# ProPrj___2025-10-22.net
KiCad netlist of a schematic drawn in EasyEDA Pro
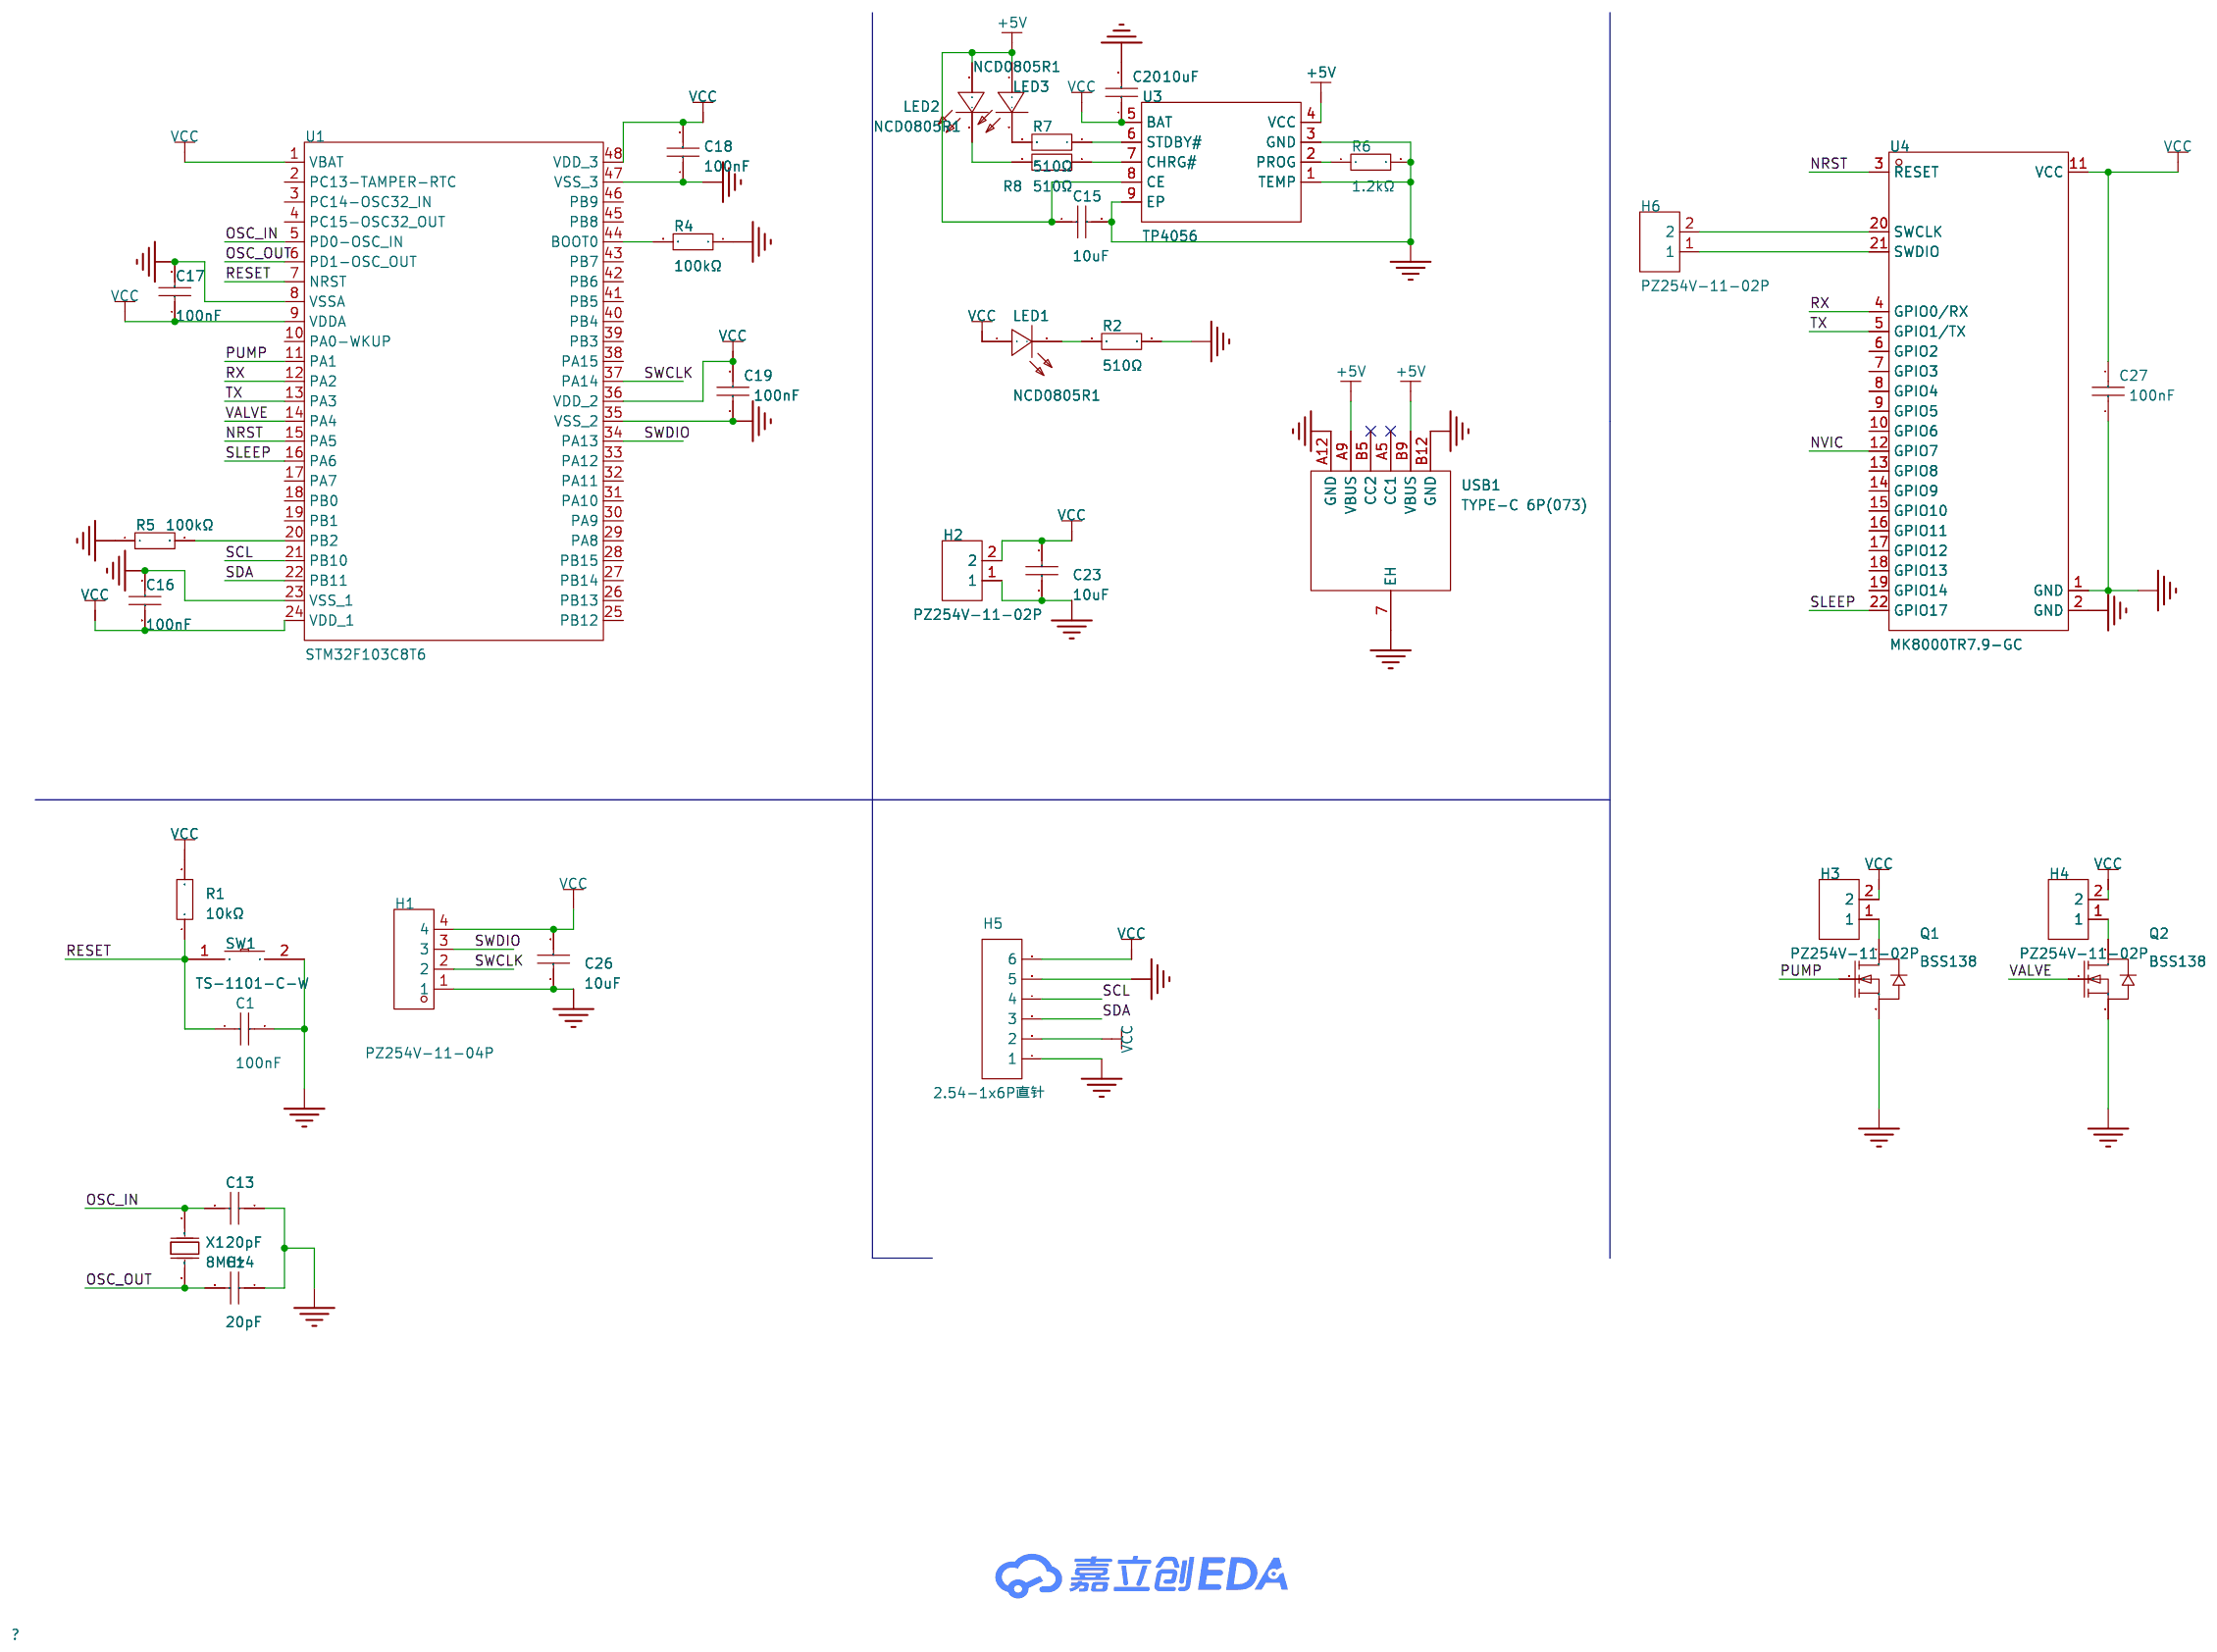
[diagram p0: schematic sheet]

(export (version "E")
  (design (tool "Eeschema 10.0.6"))
  (components
    (comp (ref "C1")
      (value "100nF")
      (footprint "easyedapro:C0805")
      (description "容值:100nF;精度:±10%;额定电压:50V;材质(温度系数):X7R;")
      (fields
        (field (name "Manufacturer Part") "CL21B104KBCNNNC")
        (field (name "Manufacturer") "SAMSUNG(三星)")
      )
      (libsource (lib "easyedapro") (part "CL21B104KBCNNNC"))
    )
    (comp (ref "C13")
      (value "20pF")
      (footprint "easyedapro:C0805")
      (description "容值:20pF;精度:±5%;额定电压:50V;材质(温度系数):C0G;")
      (fields
        (field (name "Manufacturer Part") "CL21C200JBANNNC")
        (field (name "Manufacturer") "SAMSUNG(三星)")
      )
      (libsource (lib "easyedapro") (part "CL21C200JBANNNC"))
    )
    (comp (ref "C14")
      (value "20pF")
      (footprint "easyedapro:C0805")
      (description "容值:20pF;精度:±5%;额定电压:50V;材质(温度系数):C0G;")
      (fields
        (field (name "Manufacturer Part") "CL21C200JBANNNC")
        (field (name "Manufacturer") "SAMSUNG(三星)")
      )
      (libsource (lib "easyedapro") (part "CL21C200JBANNNC"))
    )
    (comp (ref "C15")
      (value "10uF")
      (footprint "easyedapro:C0805")
      (description "容值:10uF;精度:±10%;额定电压:16V;温度系数:X5R;")
      (fields
        (field (name "Manufacturer Part") "CL21A106KOQNNNE")
        (field (name "Manufacturer") "SAMSUNG(三星)")
      )
      (libsource (lib "easyedapro") (part "CL21A106KOQNNNE"))
    )
    (comp (ref "C16")
      (value "100nF")
      (footprint "easyedapro:C0805")
      (description "容值:100nF;精度:±10%;额定电压:50V;材质(温度系数):X7R;")
      (fields
        (field (name "Manufacturer Part") "CL21B104KBCNNNC")
        (field (name "Manufacturer") "SAMSUNG(三星)")
      )
      (libsource (lib "easyedapro") (part "CL21B104KBCNNNC"))
    )
    (comp (ref "C17")
      (value "100nF")
      (footprint "easyedapro:C0805")
      (description "容值:100nF;精度:±10%;额定电压:50V;材质(温度系数):X7R;")
      (fields
        (field (name "Manufacturer Part") "CL21B104KBCNNNC")
        (field (name "Manufacturer") "SAMSUNG(三星)")
      )
      (libsource (lib "easyedapro") (part "CL21B104KBCNNNC"))
    )
    (comp (ref "C18")
      (value "100nF")
      (footprint "easyedapro:C0805")
      (description "容值:100nF;精度:±10%;额定电压:50V;材质(温度系数):X7R;")
      (fields
        (field (name "Manufacturer Part") "CL21B104KBCNNNC")
        (field (name "Manufacturer") "SAMSUNG(三星)")
      )
      (libsource (lib "easyedapro") (part "CL21B104KBCNNNC"))
    )
    (comp (ref "C19")
      (value "100nF")
      (footprint "easyedapro:C0805")
      (description "容值:100nF;精度:±10%;额定电压:50V;材质(温度系数):X7R;")
      (fields
        (field (name "Manufacturer Part") "CL21B104KBCNNNC")
        (field (name "Manufacturer") "SAMSUNG(三星)")
      )
      (libsource (lib "easyedapro") (part "CL21B104KBCNNNC"))
    )
    (comp (ref "C20")
      (value "10uF")
      (footprint "easyedapro:C0805")
      (description "容值:10uF;精度:±10%;额定电压:16V;温度系数:X5R;")
      (fields
        (field (name "Manufacturer Part") "CL21A106KOQNNNE")
        (field (name "Manufacturer") "SAMSUNG(三星)")
      )
      (libsource (lib "easyedapro") (part "CL21A106KOQNNNE"))
    )
    (comp (ref "C23")
      (value "10uF")
      (footprint "easyedapro:C0805")
      (description "容值:10uF;精度:±10%;额定电压:16V;温度系数:X5R;")
      (fields
        (field (name "Manufacturer Part") "CL21A106KOQNNNE")
        (field (name "Manufacturer") "SAMSUNG(三星)")
      )
      (libsource (lib "easyedapro") (part "CL21A106KOQNNNE"))
    )
    (comp (ref "C26")
      (value "10uF")
      (footprint "easyedapro:C0805")
      (description "容值:10uF;精度:±10%;额定电压:16V;温度系数:X5R;")
      (fields
        (field (name "Manufacturer Part") "CL21A106KOQNNNE")
        (field (name "Manufacturer") "SAMSUNG(三星)")
      )
      (libsource (lib "easyedapro") (part "CL21A106KOQNNNE"))
    )
    (comp (ref "C27")
      (value "100nF")
      (footprint "easyedapro:C0805")
      (description "容值:100nF;精度:±10%;额定电压:50V;材质(温度系数):X7R;")
      (fields
        (field (name "Manufacturer Part") "CL21B104KBCNNNC")
        (field (name "Manufacturer") "SAMSUNG(三星)")
      )
      (libsource (lib "easyedapro") (part "CL21B104KBCNNNC"))
    )
    (comp (ref "H1")
      (value "PZ254V-11-04P")
      (footprint "easyedapro:HDR-TH_4P-P2.54-V-M")
      (fields (field (name "Manufacturer") "XFCN(兴飞)"))
      (libsource (lib "easyedapro") (part "PZ254V-11-04P_C2691448"))
    )
    (comp (ref "H2")
      (value "PZ254V-11-02P")
      (footprint "easyedapro:HDR-TH_2P-P2.54-V-M")
      (fields (field (name "Manufacturer") "XFCN(兴飞)"))
      (libsource (lib "easyedapro") (part "PZ254V-11-02P"))
    )
    (comp (ref "H3")
      (value "PZ254V-11-02P")
      (footprint "easyedapro:HDR-TH_2P-P2.54-V-M")
      (fields (field (name "Manufacturer") "XFCN(兴飞)"))
      (libsource (lib "easyedapro") (part "PZ254V-11-02P"))
    )
    (comp (ref "H4")
      (value "PZ254V-11-02P")
      (footprint "easyedapro:HDR-TH_2P-P2.54-V-M")
      (fields (field (name "Manufacturer") "XFCN(兴飞)"))
      (libsource (lib "easyedapro") (part "PZ254V-11-02P"))
    )
    (comp (ref "H5")
      (value "2.54-1x6P直针")
      (footprint "easyedapro:HDR-TH_6P-P2.54-V-M-1")
      (fields (field (name "Manufacturer") "BOOMELE(博穆精密)"))
      (libsource (lib "easyedapro") (part "Header-Male-2.54_1x6"))
    )
    (comp (ref "H6")
      (value "PZ254V-11-02P")
      (footprint "easyedapro:HDR-TH_2P-P2.54-V-M")
      (fields (field (name "Manufacturer") "XFCN(兴飞)"))
      (libsource (lib "easyedapro") (part "PZ254V-11-02P"))
    )
    (comp (ref "LED1")
      (value "NCD0805R1")
      (footprint "easyedapro:LED0805-R-RD")
      (fields (field (name "Manufacturer") "国星光电"))
      (libsource (lib "easyedapro") (part "FC-2012HRK-620D"))
    )
    (comp (ref "LED2")
      (value "NCD0805R1")
      (footprint "easyedapro:LED0805-R-RD")
      (fields (field (name "Manufacturer") "国星光电"))
      (libsource (lib "easyedapro") (part "FC-2012HRK-620D"))
    )
    (comp (ref "LED3")
      (value "NCD0805R1")
      (footprint "easyedapro:LED0805-R-RD")
      (fields (field (name "Manufacturer") "国星光电"))
      (libsource (lib "easyedapro") (part "FC-2012HRK-620D"))
    )
    (comp (ref "Q1")
      (value "BSS138")
      (footprint "easyedapro:SOT-23-3_L2.9-W1.3-P1.90-LS2.4-BR")
      (fields (field (name "Manufacturer") "R+O(宏嘉诚)"))
      (libsource (lib "easyedapro") (part "BSS138_C7420339"))
    )
    (comp (ref "Q2")
      (value "BSS138")
      (footprint "easyedapro:SOT-23-3_L2.9-W1.3-P1.90-LS2.4-BR")
      (fields (field (name "Manufacturer") "R+O(宏嘉诚)"))
      (libsource (lib "easyedapro") (part "BSS138_C7420339"))
    )
    (comp (ref "R1")
      (value "10kΩ")
      (footprint "easyedapro:R0805")
      (description "电阻类型:厚膜电阻;阻值:10kΩ;精度:±1%;功率:125mW;工作电压:150V;温度系数:±100ppm/°C;")
      (fields
        (field (name "Manufacturer Part") "0805W8F1002T5E")
        (field (name "Manufacturer") "UNI-ROYAL(厚声)")
      )
      (libsource (lib "easyedapro") (part "0805W8F1002T5E"))
    )
    (comp (ref "R2")
      (value "510Ω")
      (footprint "easyedapro:R0805")
      (description "电阻类型:厚膜电阻;阻值:510Ω;精度:±1%;功率:125mW;最大工作电压:150V;温度系数:±100ppm/°C;")
      (fields
        (field (name "Manufacturer Part") "0805W8F5100T5E")
        (field (name "Manufacturer") "UNI-ROYAL(厚声)")
      )
      (libsource (lib "easyedapro") (part "0805W8F5100T5E"))
    )
    (comp (ref "R4")
      (value "100kΩ")
      (footprint "easyedapro:R0805")
      (description "电阻类型:厚膜电阻;阻值:100kΩ;精度:±1%;功率:125mW;工作电压:150V;温度系数:±100ppm/°C;")
      (fields
        (field (name "Manufacturer Part") "0805W8F1003T5E")
        (field (name "Manufacturer") "UNI-ROYAL(厚声)")
      )
      (libsource (lib "easyedapro") (part "0805W8F1003T5E_C149504"))
    )
    (comp (ref "R5")
      (value "100kΩ")
      (footprint "easyedapro:R0805")
      (description "电阻类型:厚膜电阻;阻值:100kΩ;精度:±1%;功率:125mW;工作电压:150V;温度系数:±100ppm/°C;")
      (fields
        (field (name "Manufacturer Part") "0805W8F1003T5E")
        (field (name "Manufacturer") "UNI-ROYAL(厚声)")
      )
      (libsource (lib "easyedapro") (part "0805W8F1003T5E_C149504"))
    )
    (comp (ref "R6")
      (value "1.2kΩ")
      (footprint "easyedapro:R0603")
      (description "电阻类型:厚膜电阻;阻值:1.2kΩ;精度:±1%;功率:100mW;工作电压:75V;温度系数:±100ppm/°C;")
      (fields
        (field (name "Manufacturer Part") "0603WAF1201T5E")
        (field (name "Manufacturer") "UNI-ROYAL(厚声)")
      )
      (libsource (lib "easyedapro") (part "0603WAF1201T5E"))
    )
    (comp (ref "R7")
      (value "510Ω")
      (footprint "easyedapro:R0805")
      (description "电阻类型:厚膜电阻;阻值:510Ω;精度:±1%;功率:125mW;最大工作电压:150V;温度系数:±100ppm/°C;")
      (fields
        (field (name "Manufacturer Part") "0805W8F5100T5E")
        (field (name "Manufacturer") "UNI-ROYAL(厚声)")
      )
      (libsource (lib "easyedapro") (part "0805W8F5100T5E"))
    )
    (comp (ref "R8")
      (value "510Ω")
      (footprint "easyedapro:R0805")
      (description "电阻类型:厚膜电阻;阻值:510Ω;精度:±1%;功率:125mW;最大工作电压:150V;温度系数:±100ppm/°C;")
      (fields
        (field (name "Manufacturer Part") "0805W8F5100T5E")
        (field (name "Manufacturer") "UNI-ROYAL(厚声)")
      )
      (libsource (lib "easyedapro") (part "0805W8F5100T5E"))
    )
    (comp (ref "SW1")
      (value "TS-1101-C-W")
      (footprint "easyedapro:SW-SMD_L6.0-W3.3-LS8.0")
      (fields (field (name "Manufacturer") "XKB Connectivity(中国星坤)"))
      (libsource (lib "easyedapro") (part "TS-1101-C-W"))
    )
    (comp (ref "U1")
      (value "STM32F103C8T6")
      (footprint "easyedapro:LQFP-48_L7.0-W7.0-P0.50-LS9.0-BL")
      (description "CPU内核:ARM-M3;CPU最大主频:72MHz;应用领域:-;")
      (fields (field (name "Manufacturer") "ST(意法半导体)"))
      (libsource (lib "easyedapro") (part "STM32F103C8T6"))
    )
    (comp (ref "U3")
      (value "TP4056")
      (footprint "easyedapro:ESOP-8_L4.9-W3.9-P1.27-LS6.0-BL-EP")
      (description "工作电压:3.7V~6.5V;最大充电电流:1A;电池类型:锂离子;电池节数:1;")
      (fields (field (name "Manufacturer") "UMW(友台半导体)"))
      (libsource (lib "easyedapro") (part "TP4056_C725790"))
    )
    (comp (ref "U4")
      (value "MK8000TR7.9-GC")
      (footprint "easyedapro:COMM-SMD_L26.3-W16.1_MK8000TR7.9-GC")
      (description "国产UWB测距模块电子围栏应用")
      (fields (field (name "Manufacturer") "Silicontra(硅传科技)"))
      (libsource (lib "easyedapro") (part "MK8000TR7.9-GC"))
    )
    (comp (ref "USB1")
      (value "TYPE-C 6P(073)")
      (footprint "easyedapro:TYPE-C-SMD_TYPE-C-6P-073")
      (description "连接器类型:Type-C;标准:USB 3.1;公母:母;安装方式:卧贴;触点数量:6P;端口数量:1;额定电流 - 电源:3A;工作温度范围:-25°C~+85°C;")
      (fields (field (name "Manufacturer") "SHOU HAN(首韩)"))
      (libsource (lib "easyedapro") (part "TYPE-C 6P(073)"))
    )
    (comp (ref "X1")
      (value "8MHz")
      (footprint "easyedapro:CRYSTAL-SMD_L11.5-W4.8-LS12.7")
      (description "晶振类型:贴片晶振;频率:8MHz;常温频差:±20ppm;负载电容:20pF;频率稳定度:±30ppm;")
      (fields (field (name "Manufacturer Part") "X49SM8MSD2SC") (field (name "Manufacturer") "YXC(扬兴晶振)"))
      (libsource (lib "easyedapro") (part "X49SM8MSD2SC"))
    )
  )
  (nets
    (net (code "1") (name "+5V") (class "Default")
      (node (ref "C15") (pin "1") (pinfunction "1_1") (pintype "input"))
      (node (ref "LED2") (pin "1") (pinfunction "+_1") (pintype "unspecified"))
      (node (ref "LED3") (pin "1") (pinfunction "+_1") (pintype "unspecified"))
      (node (ref "U3") (pin "4") (pinfunction "VCC_4") (pintype "unspecified"))
      (node (ref "U3") (pin "8") (pinfunction "CE_8") (pintype "unspecified"))
      (node (ref "USB1") (pin "A9") (pinfunction "VBUS_A9") (pintype "unspecified"))
      (node (ref "USB1") (pin "B9") (pinfunction "VBUS_B9") (pintype "unspecified"))
    )
    (net (code "2") (name "/NRST") (class "Default")
      (node (ref "U1") (pin "15") (pinfunction "PA5_15") (pintype "unspecified"))
      (node (ref "U4") (pin "3") (pinfunction "RESET_3") (pintype "unspecified"))
    )
    (net (code "3") (name "/NVIC") (class "Default")
      (node (ref "U4") (pin "12") (pinfunction "GPIO7_12") (pintype "unspecified"))
    )
    (net (code "4") (name "/OSC_IN") (class "Default")
      (node (ref "C13") (pin "2") (pinfunction "2_2") (pintype "input"))
      (node (ref "U1") (pin "5") (pinfunction "PD0-OSC_IN_5") (pintype "unspecified"))
      (node (ref "X1") (pin "1") (pinfunction "OSC1_1") (pintype "input"))
    )
    (net (code "5") (name "/OSC_OUT") (class "Default")
      (node (ref "C14") (pin "2") (pinfunction "2_2") (pintype "input"))
      (node (ref "U1") (pin "6") (pinfunction "PD1-OSC_OUT_6") (pintype "unspecified"))
      (node (ref "X1") (pin "2") (pinfunction "OSC2_2") (pintype "input"))
    )
    (net (code "6") (name "/PUMP") (class "Default")
      (node (ref "Q1") (pin "1") (pinfunction "G_1") (pintype "unspecified"))
      (node (ref "U1") (pin "11") (pinfunction "PA1_11") (pintype "unspecified"))
    )
    (net (code "7") (name "/RESET") (class "Default")
      (node (ref "C1") (pin "1") (pinfunction "1_1") (pintype "input"))
      (node (ref "R1") (pin "1") (pinfunction "1_1") (pintype "input"))
      (node (ref "SW1") (pin "1") (pinfunction "1_1") (pintype "unspecified"))
      (node (ref "U1") (pin "7") (pinfunction "NRST_7") (pintype "unspecified"))
    )
    (net (code "8") (name "/RX") (class "Default")
      (node (ref "U1") (pin "12") (pinfunction "PA2_12") (pintype "unspecified"))
      (node (ref "U4") (pin "4") (pinfunction "GPIO0/RX_4") (pintype "unspecified"))
    )
    (net (code "9") (name "/SCL") (class "Default")
      (node (ref "H5") (pin "4") (pinfunction "4_4") (pintype "input"))
      (node (ref "U1") (pin "21") (pinfunction "PB10_21") (pintype "unspecified"))
    )
    (net (code "10") (name "/SDA") (class "Default")
      (node (ref "H5") (pin "3") (pinfunction "3_3") (pintype "input"))
      (node (ref "U1") (pin "22") (pinfunction "PB11_22") (pintype "unspecified"))
    )
    (net (code "11") (name "/SLEEP") (class "Default")
      (node (ref "U1") (pin "16") (pinfunction "PA6_16") (pintype "unspecified"))
      (node (ref "U4") (pin "22") (pinfunction "GPIO17_22") (pintype "unspecified"))
    )
    (net (code "12") (name "/SWCLK") (class "Default")
      (node (ref "H1") (pin "2") (pinfunction "2_2") (pintype "unspecified"))
      (node (ref "U1") (pin "37") (pinfunction "PA14_37") (pintype "unspecified"))
    )
    (net (code "13") (name "/SWDIO") (class "Default")
      (node (ref "H1") (pin "3") (pinfunction "3_3") (pintype "unspecified"))
      (node (ref "U1") (pin "34") (pinfunction "PA13_34") (pintype "unspecified"))
    )
    (net (code "14") (name "/TX") (class "Default")
      (node (ref "U1") (pin "13") (pinfunction "PA3_13") (pintype "unspecified"))
      (node (ref "U4") (pin "5") (pinfunction "GPIO1/TX_5") (pintype "unspecified"))
    )
    (net (code "15") (name "/VALVE") (class "Default")
      (node (ref "Q2") (pin "1") (pinfunction "G_1") (pintype "unspecified"))
      (node (ref "U1") (pin "14") (pinfunction "PA4_14") (pintype "unspecified"))
    )
    (net (code "16") (name "GND") (class "Default")
      (node (ref "C1") (pin "2") (pinfunction "2_2") (pintype "input"))
      (node (ref "C13") (pin "1") (pinfunction "1_1") (pintype "input"))
      (node (ref "C14") (pin "1") (pinfunction "1_1") (pintype "input"))
      (node (ref "C15") (pin "2") (pinfunction "2_2") (pintype "input"))
      (node (ref "C16") (pin "1") (pinfunction "1_1") (pintype "input"))
      (node (ref "C17") (pin "2") (pinfunction "2_2") (pintype "input"))
      (node (ref "C18") (pin "1") (pinfunction "1_1") (pintype "input"))
      (node (ref "C19") (pin "1") (pinfunction "1_1") (pintype "input"))
      (node (ref "C20") (pin "2") (pinfunction "2_2") (pintype "input"))
      (node (ref "C23") (pin "1") (pinfunction "1_1") (pintype "input"))
      (node (ref "C26") (pin "1") (pinfunction "1_1") (pintype "input"))
      (node (ref "C27") (pin "1") (pinfunction "1_1") (pintype "input"))
      (node (ref "H1") (pin "1") (pinfunction "1_1") (pintype "unspecified"))
      (node (ref "H2") (pin "1") (pinfunction "1_1") (pintype "unspecified"))
      (node (ref "H5") (pin "1") (pinfunction "1_1") (pintype "input"))
      (node (ref "H5") (pin "5") (pinfunction "5_5") (pintype "input"))
      (node (ref "Q1") (pin "2") (pinfunction "S_2") (pintype "unspecified"))
      (node (ref "Q2") (pin "2") (pinfunction "S_2") (pintype "unspecified"))
      (node (ref "R2") (pin "2") (pinfunction "2_2") (pintype "input"))
      (node (ref "R4") (pin "1") (pinfunction "1_1") (pintype "unspecified"))
      (node (ref "R5") (pin "1") (pinfunction "1_1") (pintype "unspecified"))
      (node (ref "R6") (pin "2") (pinfunction "2_2") (pintype "input"))
      (node (ref "SW1") (pin "2") (pinfunction "2_2") (pintype "unspecified"))
      (node (ref "U1") (pin "23") (pinfunction "VSS_1_23") (pintype "unspecified"))
      (node (ref "U1") (pin "35") (pinfunction "VSS_2_35") (pintype "unspecified"))
      (node (ref "U1") (pin "47") (pinfunction "VSS_3_47") (pintype "unspecified"))
      (node (ref "U1") (pin "8") (pinfunction "VSSA_8") (pintype "unspecified"))
      (node (ref "U3") (pin "1") (pinfunction "TEMP_1") (pintype "unspecified"))
      (node (ref "U3") (pin "3") (pinfunction "GND_3") (pintype "unspecified"))
      (node (ref "U3") (pin "9") (pinfunction "EP_9") (pintype "unspecified"))
      (node (ref "U4") (pin "1") (pinfunction "GND_1") (pintype "unspecified"))
      (node (ref "U4") (pin "2") (pinfunction "GND_2") (pintype "unspecified"))
      (node (ref "USB1") (pin "7") (pinfunction "EH_7") (pintype "unspecified"))
      (node (ref "USB1") (pin "A12") (pinfunction "GND_A12") (pintype "unspecified"))
      (node (ref "USB1") (pin "B12") (pinfunction "GND_B12") (pintype "unspecified"))
    )
    (net (code "17") (name "Net-(LED1--)") (class "Default")
      (node (ref "LED1") (pin "2") (pinfunction "-_2") (pintype "unspecified"))
      (node (ref "R2") (pin "1") (pinfunction "1_1") (pintype "input"))
    )
    (net (code "18") (name "Net-(LED2--)") (class "Default")
      (node (ref "LED2") (pin "2") (pinfunction "-_2") (pintype "unspecified"))
      (node (ref "R8") (pin "2") (pinfunction "2_2") (pintype "input"))
    )
    (net (code "19") (name "Net-(LED3--)") (class "Default")
      (node (ref "LED3") (pin "2") (pinfunction "-_2") (pintype "unspecified"))
      (node (ref "R7") (pin "2") (pinfunction "2_2") (pintype "input"))
    )
    (net (code "20") (name "Net-(Q1-D)") (class "Default")
      (node (ref "H3") (pin "1") (pinfunction "1_1") (pintype "unspecified"))
      (node (ref "Q1") (pin "3") (pinfunction "D_3") (pintype "unspecified"))
    )
    (net (code "21") (name "Net-(Q2-D)") (class "Default")
      (node (ref "H4") (pin "1") (pinfunction "1_1") (pintype "unspecified"))
      (node (ref "Q2") (pin "3") (pinfunction "D_3") (pintype "unspecified"))
    )
    (net (code "22") (name "Net-(U1-BOOT0)") (class "Default")
      (node (ref "R4") (pin "2") (pinfunction "2_2") (pintype "unspecified"))
      (node (ref "U1") (pin "44") (pinfunction "BOOT0_44") (pintype "unspecified"))
    )
    (net (code "23") (name "Net-(U1-PB2)") (class "Default")
      (node (ref "R5") (pin "2") (pinfunction "2_2") (pintype "unspecified"))
      (node (ref "U1") (pin "20") (pinfunction "PB2_20") (pintype "unspecified"))
    )
    (net (code "24") (name "Net-(U3-CHRG#)") (class "Default")
      (node (ref "R8") (pin "1") (pinfunction "1_1") (pintype "input"))
      (node (ref "U3") (pin "7") (pinfunction "CHRG#_7") (pintype "unspecified"))
    )
    (net (code "25") (name "Net-(U3-PROG)") (class "Default")
      (node (ref "R6") (pin "1") (pinfunction "1_1") (pintype "input"))
      (node (ref "U3") (pin "2") (pinfunction "PROG_2") (pintype "unspecified"))
    )
    (net (code "26") (name "Net-(U3-STDBY#)") (class "Default")
      (node (ref "R7") (pin "1") (pinfunction "1_1") (pintype "input"))
      (node (ref "U3") (pin "6") (pinfunction "STDBY#_6") (pintype "unspecified"))
    )
    (net (code "27") (name "Net-(U4-SWCLK)") (class "Default")
      (node (ref "H6") (pin "2") (pinfunction "2_2") (pintype "unspecified"))
      (node (ref "U4") (pin "20") (pinfunction "SWCLK_20") (pintype "unspecified"))
    )
    (net (code "28") (name "Net-(U4-SWDIO)") (class "Default")
      (node (ref "H6") (pin "1") (pinfunction "1_1") (pintype "unspecified"))
      (node (ref "U4") (pin "21") (pinfunction "SWDIO_21") (pintype "unspecified"))
    )
    (net (code "29") (name "VCC") (class "Default")
      (node (ref "C16") (pin "2") (pinfunction "2_2") (pintype "input"))
      (node (ref "C17") (pin "1") (pinfunction "1_1") (pintype "input"))
      (node (ref "C18") (pin "2") (pinfunction "2_2") (pintype "input"))
      (node (ref "C19") (pin "2") (pinfunction "2_2") (pintype "input"))
      (node (ref "C20") (pin "1") (pinfunction "1_1") (pintype "input"))
      (node (ref "C23") (pin "2") (pinfunction "2_2") (pintype "input"))
      (node (ref "C26") (pin "2") (pinfunction "2_2") (pintype "input"))
      (node (ref "C27") (pin "2") (pinfunction "2_2") (pintype "input"))
      (node (ref "H1") (pin "4") (pinfunction "4_4") (pintype "unspecified"))
      (node (ref "H2") (pin "2") (pinfunction "2_2") (pintype "unspecified"))
      (node (ref "H3") (pin "2") (pinfunction "2_2") (pintype "unspecified"))
      (node (ref "H4") (pin "2") (pinfunction "2_2") (pintype "unspecified"))
      (node (ref "H5") (pin "2") (pinfunction "2_2") (pintype "input"))
      (node (ref "H5") (pin "6") (pinfunction "6_6") (pintype "input"))
      (node (ref "LED1") (pin "1") (pinfunction "+_1") (pintype "unspecified"))
      (node (ref "R1") (pin "2") (pinfunction "2_2") (pintype "input"))
      (node (ref "U1") (pin "1") (pinfunction "VBAT_1") (pintype "unspecified"))
      (node (ref "U1") (pin "24") (pinfunction "VDD_1_24") (pintype "unspecified"))
      (node (ref "U1") (pin "36") (pinfunction "VDD_2_36") (pintype "unspecified"))
      (node (ref "U1") (pin "48") (pinfunction "VDD_3_48") (pintype "unspecified"))
      (node (ref "U1") (pin "9") (pinfunction "VDDA_9") (pintype "unspecified"))
      (node (ref "U3") (pin "5") (pinfunction "BAT_5") (pintype "unspecified"))
      (node (ref "U4") (pin "11") (pinfunction "VCC_11") (pintype "unspecified"))
    )
    (net (code "30") (name "unconnected-(U1-PA0-WKUP-Pad10)") (class "Default")
      (node (ref "U1") (pin "10") (pinfunction "PA0-WKUP_10") (pintype "unspecified"))
    )
    (net (code "31") (name "unconnected-(U1-PA7-Pad17)") (class "Default")
      (node (ref "U1") (pin "17") (pinfunction "PA7_17") (pintype "unspecified"))
    )
    (net (code "32") (name "unconnected-(U1-PA8-Pad29)") (class "Default")
      (node (ref "U1") (pin "29") (pinfunction "PA8_29") (pintype "unspecified"))
    )
    (net (code "33") (name "unconnected-(U1-PA9-Pad30)") (class "Default")
      (node (ref "U1") (pin "30") (pinfunction "PA9_30") (pintype "unspecified"))
    )
    (net (code "34") (name "unconnected-(U1-PA10-Pad31)") (class "Default")
      (node (ref "U1") (pin "31") (pinfunction "PA10_31") (pintype "unspecified"))
    )
    (net (code "35") (name "unconnected-(U1-PA11-Pad32)") (class "Default")
      (node (ref "U1") (pin "32") (pinfunction "PA11_32") (pintype "unspecified"))
    )
    (net (code "36") (name "unconnected-(U1-PA12-Pad33)") (class "Default")
      (node (ref "U1") (pin "33") (pinfunction "PA12_33") (pintype "unspecified"))
    )
    (net (code "37") (name "unconnected-(U1-PA15-Pad38)") (class "Default")
      (node (ref "U1") (pin "38") (pinfunction "PA15_38") (pintype "unspecified"))
    )
    (net (code "38") (name "unconnected-(U1-PB0-Pad18)") (class "Default")
      (node (ref "U1") (pin "18") (pinfunction "PB0_18") (pintype "unspecified"))
    )
    (net (code "39") (name "unconnected-(U1-PB1-Pad19)") (class "Default")
      (node (ref "U1") (pin "19") (pinfunction "PB1_19") (pintype "unspecified"))
    )
    (net (code "40") (name "unconnected-(U1-PB3-Pad39)") (class "Default")
      (node (ref "U1") (pin "39") (pinfunction "PB3_39") (pintype "unspecified"))
    )
    (net (code "41") (name "unconnected-(U1-PB4-Pad40)") (class "Default")
      (node (ref "U1") (pin "40") (pinfunction "PB4_40") (pintype "unspecified"))
    )
    (net (code "42") (name "unconnected-(U1-PB5-Pad41)") (class "Default")
      (node (ref "U1") (pin "41") (pinfunction "PB5_41") (pintype "unspecified"))
    )
    (net (code "43") (name "unconnected-(U1-PB6-Pad42)") (class "Default")
      (node (ref "U1") (pin "42") (pinfunction "PB6_42") (pintype "unspecified"))
    )
    (net (code "44") (name "unconnected-(U1-PB7-Pad43)") (class "Default")
      (node (ref "U1") (pin "43") (pinfunction "PB7_43") (pintype "unspecified"))
    )
    (net (code "45") (name "unconnected-(U1-PB8-Pad45)") (class "Default")
      (node (ref "U1") (pin "45") (pinfunction "PB8_45") (pintype "unspecified"))
    )
    (net (code "46") (name "unconnected-(U1-PB9-Pad46)") (class "Default")
      (node (ref "U1") (pin "46") (pinfunction "PB9_46") (pintype "unspecified"))
    )
    (net (code "47") (name "unconnected-(U1-PB12-Pad25)") (class "Default")
      (node (ref "U1") (pin "25") (pinfunction "PB12_25") (pintype "unspecified"))
    )
    (net (code "48") (name "unconnected-(U1-PB13-Pad26)") (class "Default")
      (node (ref "U1") (pin "26") (pinfunction "PB13_26") (pintype "unspecified"))
    )
    (net (code "49") (name "unconnected-(U1-PB14-Pad27)") (class "Default")
      (node (ref "U1") (pin "27") (pinfunction "PB14_27") (pintype "unspecified"))
    )
    (net (code "50") (name "unconnected-(U1-PB15-Pad28)") (class "Default")
      (node (ref "U1") (pin "28") (pinfunction "PB15_28") (pintype "unspecified"))
    )
    (net (code "51") (name "unconnected-(U1-PC13-TAMPER-RTC-Pad2)") (class "Default")
      (node (ref "U1") (pin "2") (pinfunction "PC13-TAMPER-RTC_2") (pintype "unspecified"))
    )
    (net (code "52") (name "unconnected-(U1-PC14-OSC32_IN-Pad3)") (class "Default")
      (node (ref "U1") (pin "3") (pinfunction "PC14-OSC32_IN_3") (pintype "unspecified"))
    )
    (net (code "53") (name "unconnected-(U1-PC15-OSC32_OUT-Pad4)") (class "Default")
      (node (ref "U1") (pin "4") (pinfunction "PC15-OSC32_OUT_4") (pintype "unspecified"))
    )
    (net (code "54") (name "unconnected-(U4-GPIO2-Pad6)") (class "Default")
      (node (ref "U4") (pin "6") (pinfunction "GPIO2_6") (pintype "unspecified"))
    )
    (net (code "55") (name "unconnected-(U4-GPIO3-Pad7)") (class "Default")
      (node (ref "U4") (pin "7") (pinfunction "GPIO3_7") (pintype "unspecified"))
    )
    (net (code "56") (name "unconnected-(U4-GPIO4-Pad8)") (class "Default")
      (node (ref "U4") (pin "8") (pinfunction "GPIO4_8") (pintype "unspecified"))
    )
    (net (code "57") (name "unconnected-(U4-GPIO5-Pad9)") (class "Default")
      (node (ref "U4") (pin "9") (pinfunction "GPIO5_9") (pintype "unspecified"))
    )
    (net (code "58") (name "unconnected-(U4-GPIO6-Pad10)") (class "Default")
      (node (ref "U4") (pin "10") (pinfunction "GPIO6_10") (pintype "unspecified"))
    )
    (net (code "59") (name "unconnected-(U4-GPIO8-Pad13)") (class "Default")
      (node (ref "U4") (pin "13") (pinfunction "GPIO8_13") (pintype "unspecified"))
    )
    (net (code "60") (name "unconnected-(U4-GPIO9-Pad14)") (class "Default")
      (node (ref "U4") (pin "14") (pinfunction "GPIO9_14") (pintype "unspecified"))
    )
    (net (code "61") (name "unconnected-(U4-GPIO10-Pad15)") (class "Default")
      (node (ref "U4") (pin "15") (pinfunction "GPIO10_15") (pintype "unspecified"))
    )
    (net (code "62") (name "unconnected-(U4-GPIO11-Pad16)") (class "Default")
      (node (ref "U4") (pin "16") (pinfunction "GPIO11_16") (pintype "unspecified"))
    )
    (net (code "63") (name "unconnected-(U4-GPIO12-Pad17)") (class "Default")
      (node (ref "U4") (pin "17") (pinfunction "GPIO12_17") (pintype "unspecified"))
    )
    (net (code "64") (name "unconnected-(U4-GPIO13-Pad18)") (class "Default")
      (node (ref "U4") (pin "18") (pinfunction "GPIO13_18") (pintype "unspecified"))
    )
    (net (code "65") (name "unconnected-(U4-GPIO14-Pad19)") (class "Default")
      (node (ref "U4") (pin "19") (pinfunction "GPIO14_19") (pintype "unspecified"))
    )
    (net (code "66") (name "unconnected-(USB1-CC1-PadA5)") (class "Default")
      (node (ref "USB1") (pin "A5") (pinfunction "CC1_A5") (pintype "unspecified+no_connect"))
    )
    (net (code "67") (name "unconnected-(USB1-CC2-PadB5)") (class "Default")
      (node (ref "USB1") (pin "B5") (pinfunction "CC2_B5") (pintype "unspecified+no_connect"))
    )
  )
)
